# PIC-ENCODER.net
KiCad netlist of a schematic drawn in Altium Designer
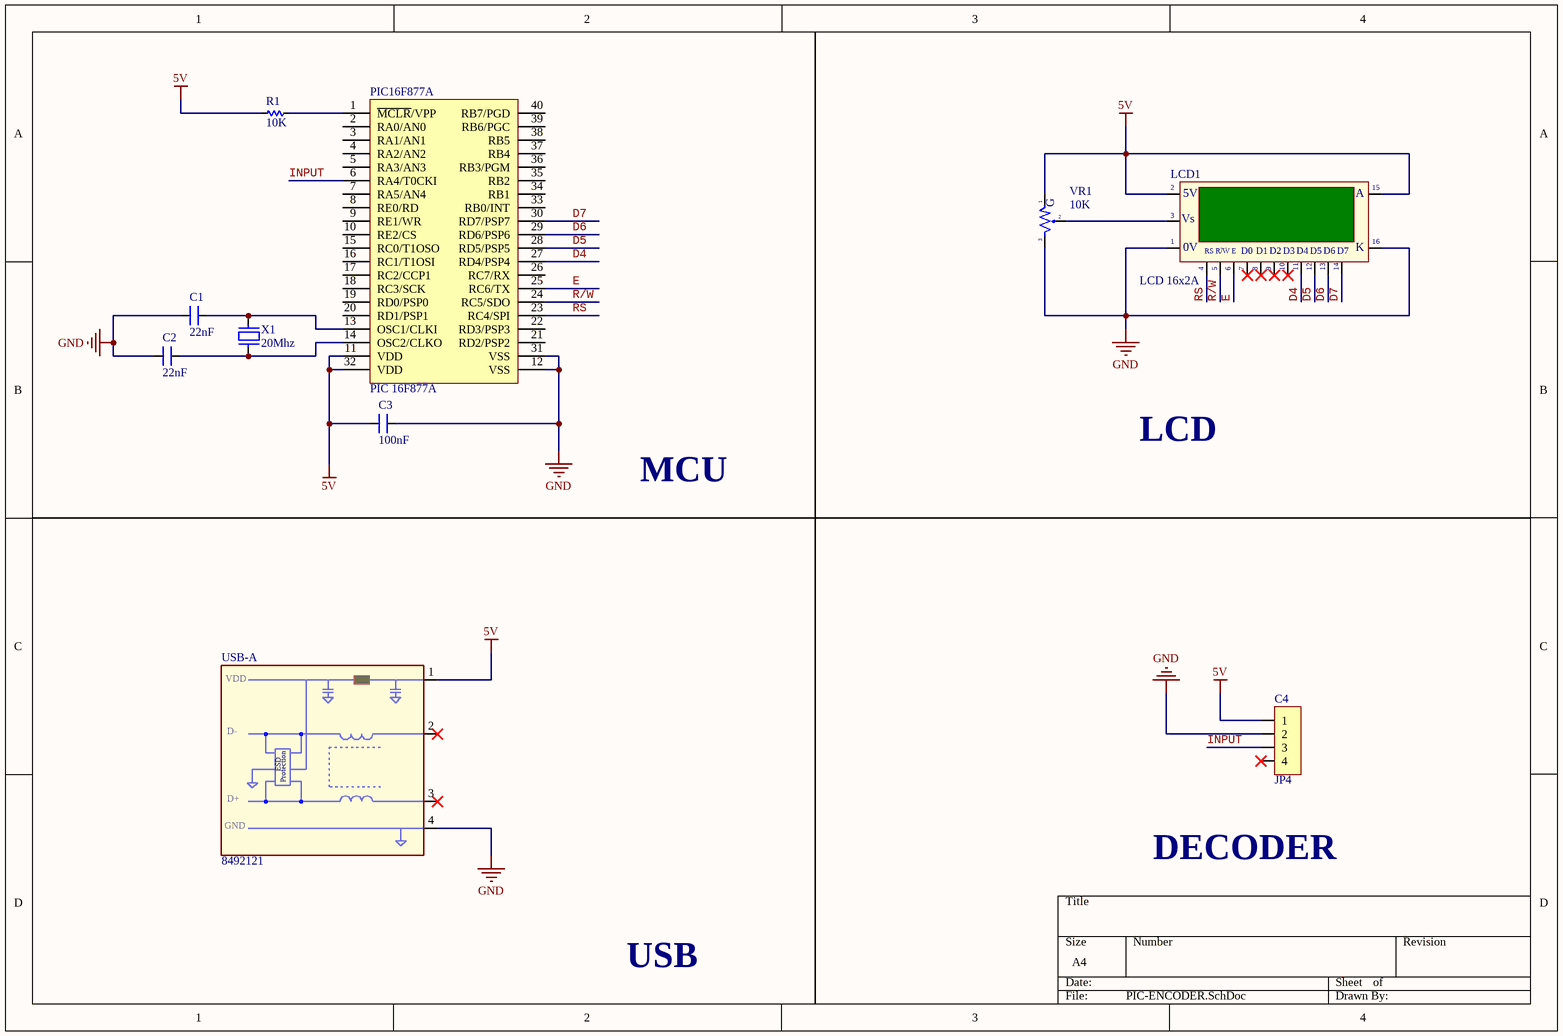
[diagram p0: PIC-ENCODER.SchDoc]

(export (version "E")
  (design (tool "Eeschema 10.0.6"))
  (components
    (comp (ref "C1") (value "22nF") (footprint "CN1.5") (libsource (lib "LIBRARY_MuaLinhKien") (part "CN")))
    (comp (ref "C2") (value "22nF") (footprint "CN1.5") (libsource (lib "LIBRARY_MuaLinhKien") (part "CN")))
    (comp (ref "C3") (value "100nF") (footprint "CN1.5") (libsource (lib "LIBRARY_MuaLinhKien") (part "CN")))
    (comp (ref "C4")
      (value "JP4")
      (footprint "JP4-C1T")
      (description "WR-PHD 2.54 mm Angled Socket Header")
      (fields
        (field (name "MANUFACTURER") "Würth Elektronik eiSos GmbH")
        (field (name "PARTNO") "613004143121")
        (field (name "CREATED BY") "Karrer Zheng")
      )
      (libsource (lib "LIBRARY_MuaLinhKien") (part "JP4"))
    )
    (comp (ref "LCD1")
      (value "LCD 16x2A")
      (footprint "LCD16X2")
      (description "LCD dipslay 16 char, 2 line")
      (libsource (lib "MinhHa_Integrated_Library") (part "LCD16x2A"))
    )
    (comp (ref "PIC16F877A")
      (value "PIC 16F877A")
      (footprint "DIP40/W0.6")
      (description "8K FLASH, 368B RAM, 256B EFROM")
      (fields (field (name "COPYRIGHT BY") "VanDungEvn"))
      (libsource (lib "LIBRARY_MuaLinhKien") (part "PIC16F877-PU"))
    )
    (comp (ref "R1")
      (value "10K")
      (footprint "RES-1/4W")
      (description "Res")
      (fields
        (field (name "MANUFACTURER") "Generic Components")
        (field (name "PUBLISHER") "Altium Hobart Technology Centre")
      )
      (libsource (lib "LIBRARY_MuaLinhKien") (part "Res"))
    )
    (comp (ref "USB-A")
      (value "8492121")
      (footprint "USB-C1")
      (description "THT USB 2.0 A Connector WE-EPLE")
      (fields
        (field (name "MANUFACTURER") "Würth Elektronik eiSos GmbH")
        (field (name "CREATED BY") "Christin Otto")
      )
      (libsource (lib "LIBRARY_MuaLinhKien") (part "USB-4"))
    )
    (comp (ref "VR1")
      (value "10K")
      (footprint "VR-S2")
      (description "Var Resistor")
      (libsource (lib "LIBRARY_MuaLinhKien") (part "VR-S"))
    )
    (comp (ref "X1")
      (value "20Mhz")
      (footprint "XT2")
      (description "Crystal, 32.768 KHz, -40 to 85 degC, 3.2 x 1.5 x 0.9 mm SMD")
      (libsource (lib "LIBRARY_MuaLinhKien") (part "XT2"))
    )
  )
  (nets
    (net (code "1") (name "/D4") (class "Default")
      (node (ref "LCD1") (pin "11") (pinfunction "D4_11") (pintype "passive"))
      (node (ref "PIC16F877A") (pin "27") (pinfunction "RD4/PSP4_27") (pintype "passive"))
    )
    (net (code "2") (name "/D5") (class "Default")
      (node (ref "LCD1") (pin "12") (pinfunction "D5_12") (pintype "passive"))
      (node (ref "PIC16F877A") (pin "28") (pinfunction "RD5/PSP5_28") (pintype "passive"))
    )
    (net (code "3") (name "/D6") (class "Default")
      (node (ref "LCD1") (pin "13") (pinfunction "D6_13") (pintype "passive"))
      (node (ref "PIC16F877A") (pin "29") (pinfunction "RD6/PSP6_29") (pintype "passive"))
    )
    (net (code "4") (name "/D7") (class "Default")
      (node (ref "LCD1") (pin "14") (pinfunction "D7_14") (pintype "passive"))
      (node (ref "PIC16F877A") (pin "30") (pinfunction "RD7/PSP7_30") (pintype "passive"))
    )
    (net (code "5") (name "/E") (class "Default")
      (node (ref "LCD1") (pin "6") (pinfunction "~{EN}_6") (pintype "passive"))
      (node (ref "PIC16F877A") (pin "25") (pinfunction "RC6/TX_25") (pintype "passive"))
    )
    (net (code "6") (name "/INPUT") (class "Default")
      (node (ref "C4") (pin "3") (pinfunction "3_3") (pintype "passive"))
      (node (ref "PIC16F877A") (pin "6") (pinfunction "RA4/T0CKI_6") (pintype "passive"))
    )
    (net (code "7") (name "/RS") (class "Default")
      (node (ref "LCD1") (pin "4") (pinfunction "RS_4") (pintype "passive"))
      (node (ref "PIC16F877A") (pin "23") (pinfunction "RC4/SPI_23") (pintype "passive"))
    )
    (net (code "8") (name "/R{slash}W") (class "Default")
      (node (ref "LCD1") (pin "5") (pinfunction "R/~{W}_5") (pintype "passive"))
      (node (ref "PIC16F877A") (pin "24") (pinfunction "RC5/SDO_24") (pintype "passive"))
    )
    (net (code "9") (name "5V") (class "Default")
      (node (ref "C3") (pin "1") (pinfunction "1_1") (pintype "passive"))
      (node (ref "C4") (pin "1") (pinfunction "1_1") (pintype "passive"))
      (node (ref "LCD1") (pin "15") (pinfunction "A_15") (pintype "passive"))
      (node (ref "LCD1") (pin "2") (pinfunction "VDD_2") (pintype "passive"))
      (node (ref "PIC16F877A") (pin "11") (pinfunction "VDD_11") (pintype "passive"))
      (node (ref "PIC16F877A") (pin "32") (pinfunction "VDD_32") (pintype "passive"))
      (node (ref "R1") (pin "2") (pinfunction "2_2") (pintype "passive"))
      (node (ref "USB-A") (pin "1") (pinfunction "VBUS_1") (pintype "passive"))
      (node (ref "VR1") (pin "1") (pinfunction "1_1") (pintype "passive"))
    )
    (net (code "10") (name "GND") (class "Default")
      (node (ref "C1") (pin "1") (pinfunction "1_1") (pintype "passive"))
      (node (ref "C2") (pin "1") (pinfunction "1_1") (pintype "passive"))
      (node (ref "C3") (pin "2") (pinfunction "2_2") (pintype "passive"))
      (node (ref "C4") (pin "2") (pinfunction "2_2") (pintype "passive"))
      (node (ref "LCD1") (pin "1") (pinfunction "GND_1") (pintype "passive"))
      (node (ref "LCD1") (pin "16") (pinfunction "K_16") (pintype "passive"))
      (node (ref "PIC16F877A") (pin "12") (pinfunction "VSS_12") (pintype "passive"))
      (node (ref "PIC16F877A") (pin "31") (pinfunction "VSS_31") (pintype "passive"))
      (node (ref "USB-A") (pin "4") (pinfunction "GND_4") (pintype "passive"))
      (node (ref "VR1") (pin "3") (pinfunction "3_3") (pintype "passive"))
    )
    (net (code "11") (name "Net-(LCD1-VEE)") (class "Default")
      (node (ref "LCD1") (pin "3") (pinfunction "VEE_3") (pintype "passive"))
      (node (ref "VR1") (pin "2") (pinfunction "2_2") (pintype "passive"))
    )
    (net (code "12") (name "Net-(PIC16F877A-OSC1{slash}CLKI)") (class "Default")
      (node (ref "C1") (pin "2") (pinfunction "2_2") (pintype "passive"))
      (node (ref "PIC16F877A") (pin "13") (pinfunction "OSC1/CLKI_13") (pintype "passive"))
      (node (ref "X1") (pin "2") (pinfunction "2_2") (pintype "passive"))
    )
    (net (code "13") (name "Net-(PIC16F877A-OSC2{slash}CLKO)") (class "Default")
      (node (ref "C2") (pin "2") (pinfunction "2_2") (pintype "passive"))
      (node (ref "PIC16F877A") (pin "14") (pinfunction "OSC2/CLKO_14") (pintype "passive"))
      (node (ref "X1") (pin "1") (pinfunction "1_1") (pintype "passive"))
    )
    (net (code "14") (name "Net-(PIC16F877A-~{MCLR}{slash}VPP)") (class "Default")
      (node (ref "PIC16F877A") (pin "1") (pinfunction "~{MCLR}/VPP_1") (pintype "passive"))
      (node (ref "R1") (pin "1") (pinfunction "1_1") (pintype "passive"))
    )
    (net (code "15") (name "unconnected-(C4-Pad4)") (class "Default")
      (node (ref "C4") (pin "4") (pinfunction "4_4") (pintype "passive+no_connect"))
    )
    (net (code "16") (name "unconnected-(LCD1-D0-Pad7)") (class "Default")
      (node (ref "LCD1") (pin "7") (pinfunction "D0_7") (pintype "passive+no_connect"))
    )
    (net (code "17") (name "unconnected-(LCD1-D1-Pad8)") (class "Default")
      (node (ref "LCD1") (pin "8") (pinfunction "D1_8") (pintype "passive+no_connect"))
    )
    (net (code "18") (name "unconnected-(LCD1-D2-Pad9)") (class "Default")
      (node (ref "LCD1") (pin "9") (pinfunction "D2_9") (pintype "passive+no_connect"))
    )
    (net (code "19") (name "unconnected-(LCD1-D3-Pad10)") (class "Default")
      (node (ref "LCD1") (pin "10") (pinfunction "D3_10") (pintype "passive+no_connect"))
    )
    (net (code "20") (name "unconnected-(PIC16F877A-RA0{slash}AN0-Pad2)") (class "Default")
      (node (ref "PIC16F877A") (pin "2") (pinfunction "RA0/AN0_2") (pintype "passive"))
    )
    (net (code "21") (name "unconnected-(PIC16F877A-RA1{slash}AN1-Pad3)") (class "Default")
      (node (ref "PIC16F877A") (pin "3") (pinfunction "RA1/AN1_3") (pintype "passive"))
    )
    (net (code "22") (name "unconnected-(PIC16F877A-RA2{slash}AN2-Pad4)") (class "Default")
      (node (ref "PIC16F877A") (pin "4") (pinfunction "RA2/AN2_4") (pintype "passive"))
    )
    (net (code "23") (name "unconnected-(PIC16F877A-RA3{slash}AN3-Pad5)") (class "Default")
      (node (ref "PIC16F877A") (pin "5") (pinfunction "RA3/AN3_5") (pintype "passive"))
    )
    (net (code "24") (name "unconnected-(PIC16F877A-RA5{slash}AN4-Pad7)") (class "Default")
      (node (ref "PIC16F877A") (pin "7") (pinfunction "RA5/AN4_7") (pintype "passive"))
    )
    (net (code "25") (name "unconnected-(PIC16F877A-RB0{slash}INT-Pad33)") (class "Default")
      (node (ref "PIC16F877A") (pin "33") (pinfunction "RB0/INT_33") (pintype "passive"))
    )
    (net (code "26") (name "unconnected-(PIC16F877A-RB1-Pad34)") (class "Default")
      (node (ref "PIC16F877A") (pin "34") (pinfunction "RB1_34") (pintype "passive"))
    )
    (net (code "27") (name "unconnected-(PIC16F877A-RB2-Pad35)") (class "Default")
      (node (ref "PIC16F877A") (pin "35") (pinfunction "RB2_35") (pintype "passive"))
    )
    (net (code "28") (name "unconnected-(PIC16F877A-RB3{slash}PGM-Pad36)") (class "Default")
      (node (ref "PIC16F877A") (pin "36") (pinfunction "RB3/PGM_36") (pintype "passive"))
    )
    (net (code "29") (name "unconnected-(PIC16F877A-RB4-Pad37)") (class "Default")
      (node (ref "PIC16F877A") (pin "37") (pinfunction "RB4_37") (pintype "passive"))
    )
    (net (code "30") (name "unconnected-(PIC16F877A-RB5-Pad38)") (class "Default")
      (node (ref "PIC16F877A") (pin "38") (pinfunction "RB5_38") (pintype "passive"))
    )
    (net (code "31") (name "unconnected-(PIC16F877A-RB6{slash}PGC-Pad39)") (class "Default")
      (node (ref "PIC16F877A") (pin "39") (pinfunction "RB6/PGC_39") (pintype "passive"))
    )
    (net (code "32") (name "unconnected-(PIC16F877A-RB7{slash}PGD-Pad40)") (class "Default")
      (node (ref "PIC16F877A") (pin "40") (pinfunction "RB7/PGD_40") (pintype "passive"))
    )
    (net (code "33") (name "unconnected-(PIC16F877A-RC0{slash}T1OSO-Pad15)") (class "Default")
      (node (ref "PIC16F877A") (pin "15") (pinfunction "RC0/T1OSO_15") (pintype "passive"))
    )
    (net (code "34") (name "unconnected-(PIC16F877A-RC1{slash}T1OSI-Pad16)") (class "Default")
      (node (ref "PIC16F877A") (pin "16") (pinfunction "RC1/T1OSI_16") (pintype "passive"))
    )
    (net (code "35") (name "unconnected-(PIC16F877A-RC2{slash}CCP1-Pad17)") (class "Default")
      (node (ref "PIC16F877A") (pin "17") (pinfunction "RC2/CCP1_17") (pintype "passive"))
    )
    (net (code "36") (name "unconnected-(PIC16F877A-RC3{slash}SCK-Pad18)") (class "Default")
      (node (ref "PIC16F877A") (pin "18") (pinfunction "RC3/SCK_18") (pintype "passive"))
    )
    (net (code "37") (name "unconnected-(PIC16F877A-RC7{slash}RX-Pad26)") (class "Default")
      (node (ref "PIC16F877A") (pin "26") (pinfunction "RC7/RX_26") (pintype "passive"))
    )
    (net (code "38") (name "unconnected-(PIC16F877A-RD0{slash}PSP0-Pad19)") (class "Default")
      (node (ref "PIC16F877A") (pin "19") (pinfunction "RD0/PSP0_19") (pintype "passive"))
    )
    (net (code "39") (name "unconnected-(PIC16F877A-RD1{slash}PSP1-Pad20)") (class "Default")
      (node (ref "PIC16F877A") (pin "20") (pinfunction "RD1/PSP1_20") (pintype "passive"))
    )
    (net (code "40") (name "unconnected-(PIC16F877A-RD2{slash}PSP2-Pad21)") (class "Default")
      (node (ref "PIC16F877A") (pin "21") (pinfunction "RD2/PSP2_21") (pintype "passive"))
    )
    (net (code "41") (name "unconnected-(PIC16F877A-RD3{slash}PSP3-Pad22)") (class "Default")
      (node (ref "PIC16F877A") (pin "22") (pinfunction "RD3/PSP3_22") (pintype "passive"))
    )
    (net (code "42") (name "unconnected-(PIC16F877A-RE0{slash}RD-Pad8)") (class "Default")
      (node (ref "PIC16F877A") (pin "8") (pinfunction "RE0/RD_8") (pintype "passive"))
    )
    (net (code "43") (name "unconnected-(PIC16F877A-RE1{slash}WR-Pad9)") (class "Default")
      (node (ref "PIC16F877A") (pin "9") (pinfunction "RE1/WR_9") (pintype "passive"))
    )
    (net (code "44") (name "unconnected-(PIC16F877A-RE2{slash}CS-Pad10)") (class "Default")
      (node (ref "PIC16F877A") (pin "10") (pinfunction "RE2/CS_10") (pintype "passive"))
    )
    (net (code "45") (name "unconnected-(USB-A-D+-Pad3)") (class "Default")
      (node (ref "USB-A") (pin "3") (pinfunction "D+_3") (pintype "passive+no_connect"))
    )
    (net (code "46") (name "unconnected-(USB-A-D--Pad2)") (class "Default")
      (node (ref "USB-A") (pin "2") (pinfunction "D-_2") (pintype "passive+no_connect"))
    )
  )
)
